# zhou_ASCII_SchDoc_2021-06-06.net
KiCad netlist of a schematic drawn in EasyEDA
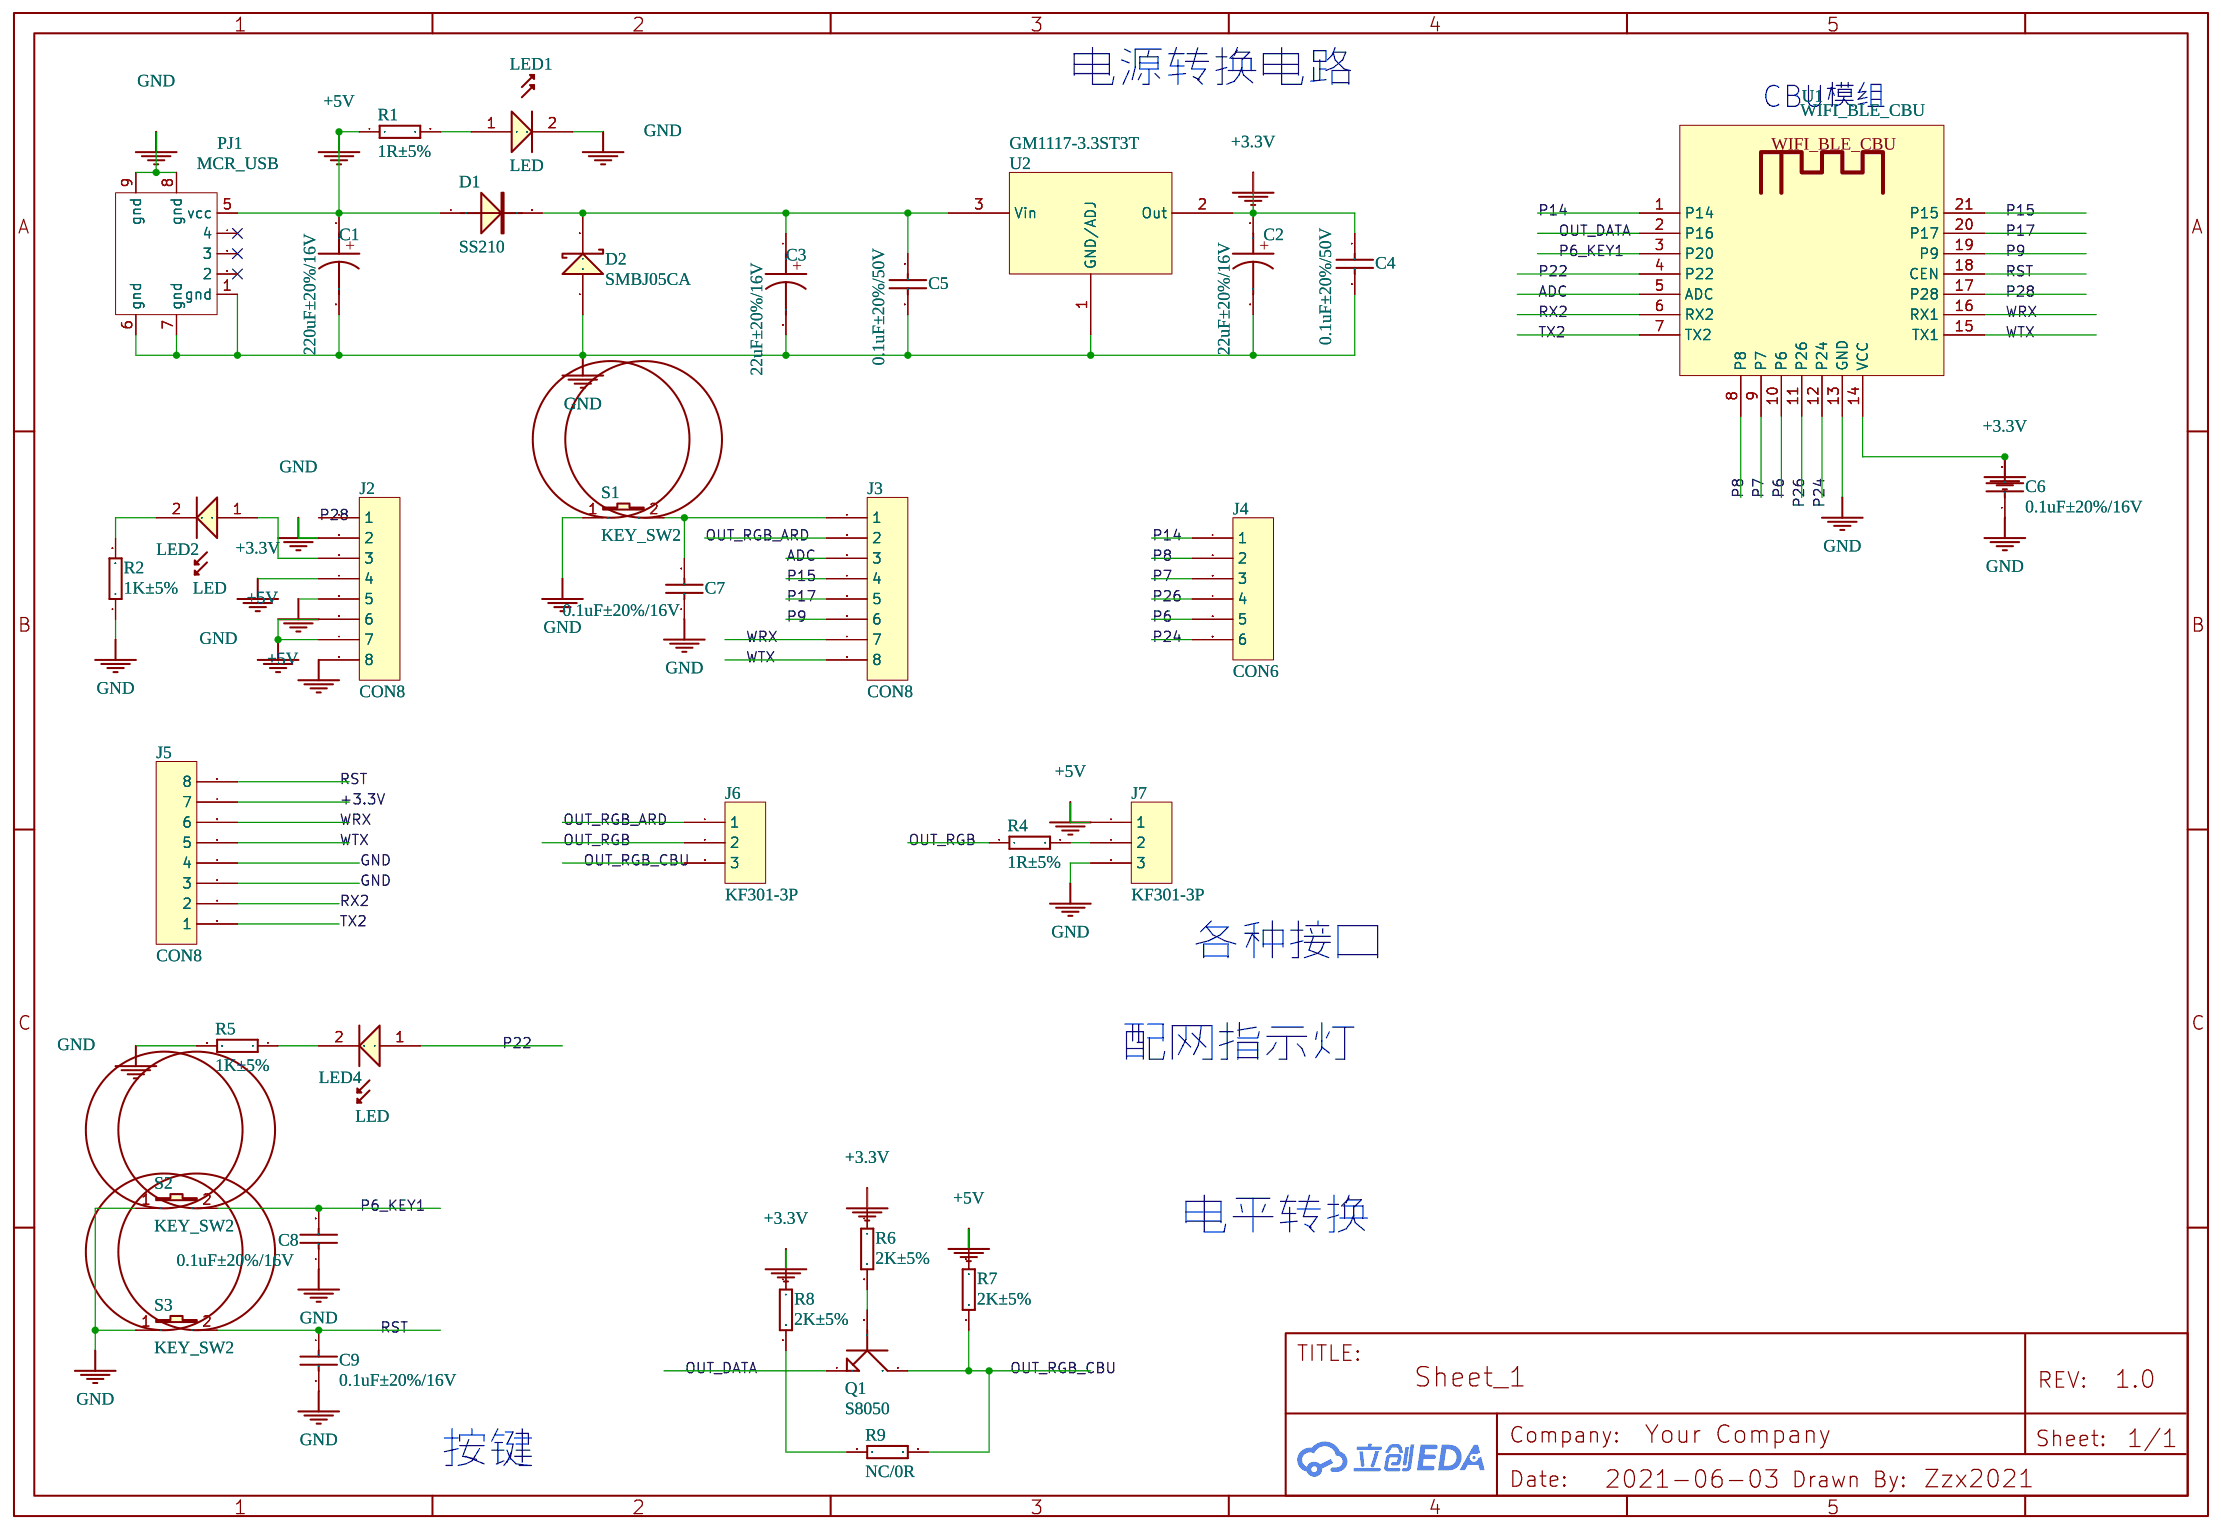
[diagram p0: schematic sheet]

(export (version "E")
  (design (tool "Eeschema 10.0.6"))
  (components
    (comp (ref "C1") (value "220uF±20%/16V") (libsource (lib "") (part "Unknown_160_-640")))
    (comp (ref "C2") (value "22uF±20%/16V") (libsource (lib "") (part "Unknown_610_-640")))
    (comp (ref "C3") (value "22uF±20%/16V") (libsource (lib "") (part "Unknown_380_-630")))
    (comp (ref "C4") (value "0.1uF±20%/50V") (libsource (lib "") (part "Unknown_660_-630")))
    (comp (ref "C5") (value "0.1uF±20%/50V") (libsource (lib "") (part "Unknown_440_-620")))
    (comp (ref "C6") (value "0.1uF±20%/16V") (libsource (lib "") (part "Unknown_1000_-510")))
    (comp (ref "C7") (value "0.1uF±20%/16V") (libsource (lib "") (part "Unknown_350_-460")))
    (comp (ref "C8") (value "0.1uF±20%/16V") (libsource (lib "") (part "Unknown_170_-140")))
    (comp (ref "C9") (value "0.1uF±20%/16V") (libsource (lib "") (part "Unknown_150_-90")))
    (comp (ref "D1") (value "SS210") (libsource (lib "") (part "Unknown_240_-650")))
    (comp (ref "D2") (value "SMBJ05CA") (libsource (lib "") (part "Unknown_280_-620")))
    (comp (ref "J2") (value "CON8") (libsource (lib "") (part "Unknown_180_-510")))
    (comp (ref "J3") (value "CON8") (libsource (lib "") (part "Unknown_430_-510")))
    (comp (ref "J4") (value "CON6") (libsource (lib "") (part "Unknown_610_-500")))
    (comp (ref "J5") (value "CON8") (libsource (lib "") (part "Unknown_100_-290")))
    (comp (ref "J6") (value "KF301-3P") (libsource (lib "") (part "Unknown_360_-360")))
    (comp (ref "J7") (value "KF301-3P") (libsource (lib "") (part "Unknown_560_-360")))
    (comp (ref "LED1") (value "LED") (libsource (lib "") (part "Unknown_255_-700")))
    (comp (ref "LED2") (value "LED") (libsource (lib "") (part "Unknown_110_-490")))
    (comp (ref "LED4") (value "LED") (libsource (lib "") (part "Unknown_190_-230")))
    (comp (ref "PJ1") (value "MCR_USB") (libsource (lib "") (part "Unknown_60_-660")))
    (comp (ref "Q1") (value "S8050") (libsource (lib "") (part "Unknown_440_-100")))
    (comp (ref "R1") (value "1R±5%") (libsource (lib "") (part "Unknown_200_-690")))
    (comp (ref "R2") (value "1K±5%") (libsource (lib "") (part "Unknown_60_-470")))
    (comp (ref "R4") (value "1R±5%") (libsource (lib "") (part "Unknown_510_-340")))
    (comp (ref "R5") (value "1K±5%") (libsource (lib "") (part "Unknown_120_-240")))
    (comp (ref "R6") (value "2K±5%") (libsource (lib "") (part "Unknown_430_-140")))
    (comp (ref "R7") (value "2K±5%") (libsource (lib "") (part "Unknown_480_-120")))
    (comp (ref "R8") (value "2K±5%") (libsource (lib "") (part "Unknown_390_-110")))
    (comp (ref "R9") (value "NC/0R") (libsource (lib "") (part "Unknown_440_-40")))
    (comp (ref "S1") (value "KEY_SW2") (libsource (lib "") (part "Unknown_300_-510")))
    (comp (ref "S2") (value "KEY_SW2") (libsource (lib "") (part "Unknown_80_-170")))
    (comp (ref "S3") (value "KEY_SW2") (libsource (lib "") (part "Unknown_80_-110")))
    (comp (ref "U1") (value "WIFI_BLE_CBU") (libsource (lib "") (part "Unknown_830_-570")))
    (comp (ref "U2") (value "GM1117-3.3ST3T") (libsource (lib "") (part "Unknown_540_-640")))
  )
  (nets
    (net (code "1") (name "+3.3V") (class "Default")
      (node (ref "C2") (pin "1") (pinfunction "1_1") (pintype "unspecified"))
      (node (ref "C4") (pin "1") (pinfunction "1_1") (pintype "unspecified"))
      (node (ref "C6") (pin "2") (pinfunction "2_2") (pintype "unspecified"))
      (node (ref "J2") (pin "4") (pinfunction "4_4") (pintype "unspecified"))
      (node (ref "J5") (pin "7") (pinfunction "7_7") (pintype "unspecified"))
      (node (ref "R6") (pin "1") (pinfunction "1_1") (pintype "unspecified"))
      (node (ref "R8") (pin "1") (pinfunction "1_1") (pintype "unspecified"))
      (node (ref "U1") (pin "14") (pinfunction "VCC_14") (pintype "unspecified"))
      (node (ref "U2") (pin "2") (pinfunction "Out_2") (pintype "unspecified"))
    )
    (net (code "2") (name "+5V") (class "Default")
      (node (ref "C1") (pin "1") (pinfunction "1_1") (pintype "unspecified"))
      (node (ref "D1") (pin "1") (pinfunction "1_1") (pintype "unspecified"))
      (node (ref "J2") (pin "5") (pinfunction "5_5") (pintype "unspecified"))
      (node (ref "J2") (pin "8") (pinfunction "8_8") (pintype "unspecified"))
      (node (ref "J7") (pin "1") (pinfunction "1_1") (pintype "unspecified"))
      (node (ref "PJ1") (pin "5") (pinfunction "vcc_5") (pintype "unspecified"))
      (node (ref "R1") (pin "1") (pinfunction "1_1") (pintype "unspecified"))
      (node (ref "R7") (pin "1") (pinfunction "1_1") (pintype "unspecified"))
    )
    (net (code "3") (name "/ADC") (class "Default")
      (node (ref "J3") (pin "3") (pinfunction "3_3") (pintype "unspecified"))
      (node (ref "U1") (pin "5") (pinfunction "ADC_5") (pintype "unspecified"))
    )
    (net (code "4") (name "/OUT_DATA") (class "Default")
      (node (ref "Q1") (pin "1") (pinfunction "E_1") (pintype "unspecified"))
      (node (ref "R8") (pin "2") (pinfunction "2_2") (pintype "unspecified"))
      (node (ref "R9") (pin "1") (pinfunction "1_1") (pintype "unspecified"))
      (node (ref "U1") (pin "2") (pinfunction "P16_2") (pintype "unspecified"))
    )
    (net (code "5") (name "/OUT_RGB") (class "Default")
      (node (ref "J6") (pin "2") (pinfunction "2_2") (pintype "unspecified"))
      (node (ref "R4") (pin "1") (pinfunction "1_1") (pintype "unspecified"))
    )
    (net (code "6") (name "/OUT_RGB_ARD") (class "Default")
      (node (ref "J3") (pin "2") (pinfunction "2_2") (pintype "unspecified"))
      (node (ref "J6") (pin "1") (pinfunction "1_1") (pintype "unspecified"))
    )
    (net (code "7") (name "/OUT_RGB_CBU") (class "Default")
      (node (ref "J6") (pin "3") (pinfunction "3_3") (pintype "unspecified"))
      (node (ref "Q1") (pin "3") (pinfunction "C_3") (pintype "unspecified"))
      (node (ref "R7") (pin "2") (pinfunction "2_2") (pintype "unspecified"))
      (node (ref "R9") (pin "2") (pinfunction "2_2") (pintype "unspecified"))
    )
    (net (code "8") (name "/P6") (class "Default")
      (node (ref "J4") (pin "5") (pinfunction "5_5") (pintype "unspecified"))
      (node (ref "U1") (pin "10") (pinfunction "P6_10") (pintype "unspecified"))
    )
    (net (code "9") (name "/P6_KEY1") (class "Default")
      (node (ref "C8") (pin "2") (pinfunction "2_2") (pintype "unspecified"))
      (node (ref "S2") (pin "2") (pinfunction "2_2") (pintype "unspecified"))
      (node (ref "U1") (pin "3") (pinfunction "P20_3") (pintype "unspecified"))
    )
    (net (code "10") (name "/P7") (class "Default")
      (node (ref "J4") (pin "3") (pinfunction "3_3") (pintype "unspecified"))
      (node (ref "U1") (pin "9") (pinfunction "P7_9") (pintype "unspecified"))
    )
    (net (code "11") (name "/P8") (class "Default")
      (node (ref "J4") (pin "2") (pinfunction "2_2") (pintype "unspecified"))
      (node (ref "U1") (pin "8") (pinfunction "P8_8") (pintype "unspecified"))
    )
    (net (code "12") (name "/P9") (class "Default")
      (node (ref "J3") (pin "6") (pinfunction "6_6") (pintype "unspecified"))
      (node (ref "U1") (pin "19") (pinfunction "P9_19") (pintype "unspecified"))
    )
    (net (code "13") (name "/P14") (class "Default")
      (node (ref "J4") (pin "1") (pinfunction "1_1") (pintype "unspecified"))
      (node (ref "U1") (pin "1") (pinfunction "P14_1") (pintype "unspecified"))
    )
    (net (code "14") (name "/P15") (class "Default")
      (node (ref "J3") (pin "4") (pinfunction "4_4") (pintype "unspecified"))
      (node (ref "U1") (pin "21") (pinfunction "P15_21") (pintype "unspecified"))
    )
    (net (code "15") (name "/P17") (class "Default")
      (node (ref "J3") (pin "5") (pinfunction "5_5") (pintype "unspecified"))
      (node (ref "U1") (pin "20") (pinfunction "P17_20") (pintype "unspecified"))
    )
    (net (code "16") (name "/P22") (class "Default")
      (node (ref "LED4") (pin "1") (pinfunction "1_1") (pintype "unspecified"))
      (node (ref "U1") (pin "4") (pinfunction "P22_4") (pintype "unspecified"))
    )
    (net (code "17") (name "/P24") (class "Default")
      (node (ref "J4") (pin "6") (pinfunction "6_6") (pintype "unspecified"))
      (node (ref "U1") (pin "12") (pinfunction "P24_12") (pintype "unspecified"))
    )
    (net (code "18") (name "/P26") (class "Default")
      (node (ref "J4") (pin "4") (pinfunction "4_4") (pintype "unspecified"))
      (node (ref "U1") (pin "11") (pinfunction "P26_11") (pintype "unspecified"))
    )
    (net (code "19") (name "/P28") (class "Default")
      (node (ref "J2") (pin "1") (pinfunction "1_1") (pintype "unspecified"))
      (node (ref "U1") (pin "17") (pinfunction "P28_17") (pintype "unspecified"))
    )
    (net (code "20") (name "/RST") (class "Default")
      (node (ref "C9") (pin "1") (pinfunction "1_1") (pintype "unspecified"))
      (node (ref "J5") (pin "8") (pinfunction "8_8") (pintype "unspecified"))
      (node (ref "S3") (pin "2") (pinfunction "2_2") (pintype "unspecified"))
      (node (ref "U1") (pin "18") (pinfunction "CEN_18") (pintype "unspecified"))
    )
    (net (code "21") (name "/RX2") (class "Default")
      (node (ref "J5") (pin "2") (pinfunction "2_2") (pintype "unspecified"))
      (node (ref "U1") (pin "6") (pinfunction "RX2_6") (pintype "unspecified"))
    )
    (net (code "22") (name "/TX2") (class "Default")
      (node (ref "J5") (pin "1") (pinfunction "1_1") (pintype "unspecified"))
      (node (ref "U1") (pin "7") (pinfunction "TX2_7") (pintype "unspecified"))
    )
    (net (code "23") (name "/WRX") (class "Default")
      (node (ref "J3") (pin "7") (pinfunction "7_7") (pintype "unspecified"))
      (node (ref "J5") (pin "6") (pinfunction "6_6") (pintype "unspecified"))
      (node (ref "U1") (pin "16") (pinfunction "RX1_16") (pintype "unspecified"))
    )
    (net (code "24") (name "/WTX") (class "Default")
      (node (ref "J3") (pin "8") (pinfunction "8_8") (pintype "unspecified"))
      (node (ref "J5") (pin "5") (pinfunction "5_5") (pintype "unspecified"))
      (node (ref "U1") (pin "15") (pinfunction "TX1_15") (pintype "unspecified"))
    )
    (net (code "25") (name "GND") (class "Default")
      (node (ref "C1") (pin "2") (pinfunction "2_2") (pintype "unspecified"))
      (node (ref "C2") (pin "2") (pinfunction "2_2") (pintype "unspecified"))
      (node (ref "C3") (pin "2") (pinfunction "2_2") (pintype "unspecified"))
      (node (ref "C4") (pin "2") (pinfunction "2_2") (pintype "unspecified"))
      (node (ref "C5") (pin "2") (pinfunction "2_2") (pintype "unspecified"))
      (node (ref "C6") (pin "1") (pinfunction "1_1") (pintype "unspecified"))
      (node (ref "C7") (pin "1") (pinfunction "1_1") (pintype "unspecified"))
      (node (ref "C8") (pin "1") (pinfunction "1_1") (pintype "unspecified"))
      (node (ref "C9") (pin "2") (pinfunction "2_2") (pintype "unspecified"))
      (node (ref "D2") (pin "1") (pinfunction "A_1") (pintype "unspecified"))
      (node (ref "J2") (pin "2") (pinfunction "2_2") (pintype "unspecified"))
      (node (ref "J2") (pin "6") (pinfunction "6_6") (pintype "unspecified"))
      (node (ref "J2") (pin "7") (pinfunction "7_7") (pintype "unspecified"))
      (node (ref "J5") (pin "3") (pinfunction "3_3") (pintype "unspecified"))
      (node (ref "J5") (pin "4") (pinfunction "4_4") (pintype "unspecified"))
      (node (ref "J7") (pin "3") (pinfunction "3_3") (pintype "unspecified"))
      (node (ref "LED1") (pin "2") (pinfunction "2_2") (pintype "unspecified"))
      (node (ref "PJ1") (pin "1") (pinfunction "gnd_1") (pintype "unspecified"))
      (node (ref "PJ1") (pin "6") (pinfunction "gnd_6") (pintype "unspecified"))
      (node (ref "PJ1") (pin "7") (pinfunction "gnd_7") (pintype "unspecified"))
      (node (ref "PJ1") (pin "8") (pinfunction "gnd_8") (pintype "unspecified"))
      (node (ref "PJ1") (pin "9") (pinfunction "gnd_9") (pintype "unspecified"))
      (node (ref "R2") (pin "1") (pinfunction "1_1") (pintype "unspecified"))
      (node (ref "R5") (pin "2") (pinfunction "2_2") (pintype "unspecified"))
      (node (ref "S1") (pin "1") (pinfunction "1_1") (pintype "unspecified"))
      (node (ref "S2") (pin "1") (pinfunction "1_1") (pintype "unspecified"))
      (node (ref "S3") (pin "1") (pinfunction "1_1") (pintype "unspecified"))
      (node (ref "U1") (pin "13") (pinfunction "GND_13") (pintype "unspecified"))
      (node (ref "U2") (pin "1") (pinfunction "GND/ADJ_1") (pintype "unspecified"))
    )
    (net (code "26") (name "Net-(C7-Pad2)") (class "Default")
      (node (ref "C7") (pin "2") (pinfunction "2_2") (pintype "unspecified"))
      (node (ref "J3") (pin "1") (pinfunction "1_1") (pintype "unspecified"))
      (node (ref "S1") (pin "2") (pinfunction "2_2") (pintype "unspecified"))
    )
    (net (code "27") (name "Net-(D2-K)") (class "Default")
      (node (ref "C3") (pin "1") (pinfunction "1_1") (pintype "unspecified"))
      (node (ref "C5") (pin "1") (pinfunction "1_1") (pintype "unspecified"))
      (node (ref "D1") (pin "2") (pinfunction "2_2") (pintype "unspecified"))
      (node (ref "D2") (pin "2") (pinfunction "K_2") (pintype "unspecified"))
      (node (ref "U2") (pin "3") (pinfunction "Vin_3") (pintype "unspecified"))
    )
    (net (code "28") (name "Net-(J2-Pad3)") (class "Default")
      (node (ref "J2") (pin "3") (pinfunction "3_3") (pintype "unspecified"))
      (node (ref "LED2") (pin "1") (pinfunction "1_1") (pintype "unspecified"))
    )
    (net (code "29") (name "Net-(J7-Pad2)") (class "Default")
      (node (ref "J7") (pin "2") (pinfunction "2_2") (pintype "unspecified"))
      (node (ref "R4") (pin "2") (pinfunction "2_2") (pintype "unspecified"))
    )
    (net (code "30") (name "Net-(LED1-Pad1)") (class "Default")
      (node (ref "LED1") (pin "1") (pinfunction "1_1") (pintype "unspecified"))
      (node (ref "R1") (pin "2") (pinfunction "2_2") (pintype "unspecified"))
    )
    (net (code "31") (name "Net-(LED2-Pad2)") (class "Default")
      (node (ref "LED2") (pin "2") (pinfunction "2_2") (pintype "unspecified"))
      (node (ref "R2") (pin "2") (pinfunction "2_2") (pintype "unspecified"))
    )
    (net (code "32") (name "Net-(LED4-Pad2)") (class "Default")
      (node (ref "LED4") (pin "2") (pinfunction "2_2") (pintype "unspecified"))
      (node (ref "R5") (pin "1") (pinfunction "1_1") (pintype "unspecified"))
    )
    (net (code "33") (name "Net-(Q1-B)") (class "Default")
      (node (ref "Q1") (pin "2") (pinfunction "B_2") (pintype "input"))
      (node (ref "R6") (pin "2") (pinfunction "2_2") (pintype "unspecified"))
    )
    (net (code "34") (name "unconnected-(PJ1-Pad2)") (class "Default")
      (node (ref "PJ1") (pin "2") (pinfunction "2_2") (pintype "unspecified+no_connect"))
    )
    (net (code "35") (name "unconnected-(PJ1-Pad3)") (class "Default")
      (node (ref "PJ1") (pin "3") (pinfunction "3_3") (pintype "unspecified+no_connect"))
    )
    (net (code "36") (name "unconnected-(PJ1-Pad4)") (class "Default")
      (node (ref "PJ1") (pin "4") (pinfunction "4_4") (pintype "unspecified+no_connect"))
    )
  )
)
